# M9A_12_3190102060_A.net
KiCad netlist of a schematic drawn in Altium Designer
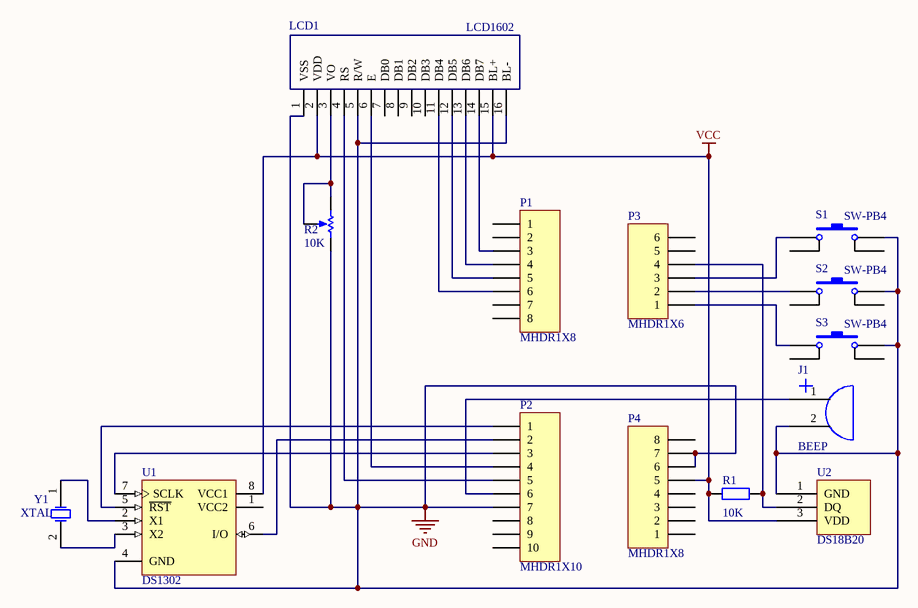
[diagram p0: M9A_12_3190102060_A.SchDoc]

(export (version "E")
  (design (tool "Eeschema 10.0.6"))
  (components
    (comp (ref "J1")
      (value "BEEP")
      (footprint "Beep")
      (description "蜂鸣器")
      (libsource (lib "Fszhang") (part "BEEP"))
    )
    (comp (ref "LCD1") (value "LCD1602") (footprint "1602") (libsource (lib "LCD") (part "LCD1602")))
    (comp (ref "P1")
      (value "MHDR1X8")
      (footprint "HDR1X8")
      (description "Header, 8-Pin")
      (fields (field (name "PUBLISHER") "Altium Limited"))
      (libsource (lib "Miscellaneous Connectors") (part "MHDR1X8"))
    )
    (comp (ref "P2")
      (value "MHDR1X10")
      (footprint "HDR1X10")
      (description "Header, 10-Pin")
      (fields (field (name "PUBLISHER") "Altium Limited"))
      (libsource (lib "Miscellaneous Connectors") (part "MHDR1X10"))
    )
    (comp (ref "P3")
      (value "MHDR1X6")
      (footprint "HDR1X6")
      (description "Header, 6-Pin")
      (fields (field (name "PUBLISHER") "Altium Limited"))
      (libsource (lib "Miscellaneous Connectors") (part "MHDR1X6"))
    )
    (comp (ref "P4")
      (value "MHDR1X8")
      (footprint "HDR1X8")
      (description "Header, 8-Pin")
      (fields (field (name "PUBLISHER") "Altium Limited"))
      (libsource (lib "") (part "MHDR1X8_1"))
    )
    (comp (ref "R1")
      (value "10K")
      (footprint "AXIAL-0.4")
      (description "Resistor")
      (fields (field (name "Comment") "Res2") (field (name "PUBLISHER") "Altium Limited"))
      (libsource (lib "Miscellaneous Devices") (part "Res2"))
    )
    (comp (ref "R2")
      (value "10K")
      (footprint "VR_A1")
      (description "精密可调电阻")
      (fields (field (name "Comment") "RPot") (field (name "PUBLISHER") "Altium Limited"))
      (libsource (lib "Fszhang") (part "RPot"))
    )
    (comp (ref "S1")
      (value "SW-PB4")
      (footprint "AN-S")
      (description "微动开关")
      (fields (field (name "PUBLISHER") "Altium Limited"))
      (libsource (lib "Fszhang") (part "SW-PB4"))
    )
    (comp (ref "S2")
      (value "SW-PB4")
      (footprint "AN-S")
      (description "微动开关")
      (fields (field (name "PUBLISHER") "Altium Limited"))
      (libsource (lib "Fszhang") (part "SW-PB4"))
    )
    (comp (ref "S3")
      (value "SW-PB4")
      (footprint "AN-S")
      (description "微动开关")
      (fields (field (name "PUBLISHER") "Altium Limited"))
      (libsource (lib "Fszhang") (part "SW-PB4"))
    )
    (comp (ref "U1")
      (value "DS1302")
      (footprint "DIP8")
      (description "Trickle Charge Timekeeping Chip")
      (fields (field (name "PUBLISHER") "Altium Limited"))
      (libsource (lib "Dallas Peripheral Real Time Clock") (part "DS1302"))
    )
    (comp (ref "U2")
      (value "DS18B20")
      (footprint "TO-92A")
      (description "温度传感器")
      (libsource (lib "Fszhang") (part "DS18B20"))
    )
    (comp (ref "Y1")
      (value "XTAL")
      (footprint "R38")
      (description "Crystal Oscillator")
      (fields (field (name "PUBLISHER") "Altium Limited"))
      (libsource (lib "Miscellaneous Devices") (part "XTAL"))
    )
  )
  (nets
    (net (code "1") (name "GND") (class "Default")
      (node (ref "J1") (pin "2") (pinfunction "1_2") (pintype "passive"))
      (node (ref "LCD1") (pin "1") (pinfunction "VSS_1") (pintype "passive"))
      (node (ref "LCD1") (pin "16") (pinfunction "BL-_16") (pintype "passive"))
      (node (ref "LCD1") (pin "5") (pinfunction "R/W_5") (pintype "passive"))
      (node (ref "P2") (pin "7") (pinfunction "7_7") (pintype "passive"))
      (node (ref "P4") (pin "6") (pinfunction "6_6") (pintype "passive"))
      (node (ref "P4") (pin "7") (pinfunction "7_7") (pintype "passive"))
      (node (ref "R2") (pin "3") (pinfunction "BOT_3") (pintype "passive"))
      (node (ref "S1") (pin "2") (pinfunction "2_2") (pintype "passive"))
      (node (ref "S2") (pin "2") (pinfunction "2_2") (pintype "passive"))
      (node (ref "S3") (pin "2") (pinfunction "2_2") (pintype "passive"))
      (node (ref "U1") (pin "4") (pinfunction "GND_4") (pintype "power_in"))
      (node (ref "U2") (pin "1") (pinfunction "GND_1") (pintype "passive"))
    )
    (net (code "2") (name "Net-(J1-0)") (class "Default")
      (node (ref "J1") (pin "1") (pinfunction "0_1") (pintype "passive"))
      (node (ref "P2") (pin "6") (pinfunction "6_6") (pintype "passive"))
    )
    (net (code "3") (name "Net-(LCD1-DB4)") (class "Default")
      (node (ref "LCD1") (pin "11") (pinfunction "DB4_11") (pintype "passive"))
      (node (ref "P1") (pin "6") (pinfunction "6_6") (pintype "passive"))
    )
    (net (code "4") (name "Net-(LCD1-DB5)") (class "Default")
      (node (ref "LCD1") (pin "12") (pinfunction "DB5_12") (pintype "passive"))
      (node (ref "P1") (pin "5") (pinfunction "5_5") (pintype "passive"))
    )
    (net (code "5") (name "Net-(LCD1-DB6)") (class "Default")
      (node (ref "LCD1") (pin "13") (pinfunction "DB6_13") (pintype "passive"))
      (node (ref "P1") (pin "4") (pinfunction "4_4") (pintype "passive"))
    )
    (net (code "6") (name "Net-(LCD1-DB7)") (class "Default")
      (node (ref "LCD1") (pin "14") (pinfunction "DB7_14") (pintype "passive"))
      (node (ref "P1") (pin "3") (pinfunction "3_3") (pintype "passive"))
    )
    (net (code "7") (name "Net-(LCD1-E)") (class "Default")
      (node (ref "LCD1") (pin "6") (pinfunction "E_6") (pintype "passive"))
      (node (ref "P2") (pin "4") (pinfunction "4_4") (pintype "passive"))
    )
    (net (code "8") (name "Net-(LCD1-RS)") (class "Default")
      (node (ref "LCD1") (pin "4") (pinfunction "RS_4") (pintype "passive"))
      (node (ref "P2") (pin "5") (pinfunction "5_5") (pintype "passive"))
    )
    (net (code "9") (name "Net-(LCD1-VO)") (class "Default")
      (node (ref "LCD1") (pin "3") (pinfunction "VO_3") (pintype "passive"))
      (node (ref "R2") (pin "1") (pinfunction "TOP_1") (pintype "passive"))
      (node (ref "R2") (pin "2") (pinfunction "TAP_2") (pintype "passive"))
    )
    (net (code "10") (name "Net-(P3-Pad1)") (class "Default")
      (node (ref "P3") (pin "1") (pinfunction "1_1") (pintype "passive"))
      (node (ref "S3") (pin "1") (pinfunction "1_1") (pintype "passive"))
    )
    (net (code "11") (name "Net-(P3-Pad2)") (class "Default")
      (node (ref "P3") (pin "2") (pinfunction "2_2") (pintype "passive"))
      (node (ref "S2") (pin "1") (pinfunction "1_1") (pintype "passive"))
    )
    (net (code "12") (name "Net-(P3-Pad3)") (class "Default")
      (node (ref "P3") (pin "3") (pinfunction "3_3") (pintype "passive"))
      (node (ref "S1") (pin "1") (pinfunction "1_1") (pintype "passive"))
    )
    (net (code "13") (name "Net-(U1-I{slash}O)") (class "Default")
      (node (ref "P2") (pin "2") (pinfunction "2_2") (pintype "passive"))
      (node (ref "U1") (pin "6") (pinfunction "I/O_6") (pintype "bidirectional"))
    )
    (net (code "14") (name "Net-(U1-SCLK)") (class "Default")
      (node (ref "P2") (pin "3") (pinfunction "3_3") (pintype "passive"))
      (node (ref "U1") (pin "7") (pinfunction "SCLK_7") (pintype "input"))
    )
    (net (code "15") (name "Net-(U1-X1)") (class "Default")
      (node (ref "U1") (pin "2") (pinfunction "X1_2") (pintype "input"))
      (node (ref "Y1") (pin "1") (pinfunction "OSC1_1") (pintype "passive"))
    )
    (net (code "16") (name "Net-(U1-X2)") (class "Default")
      (node (ref "U1") (pin "3") (pinfunction "X2_3") (pintype "input"))
      (node (ref "Y1") (pin "2") (pinfunction "OSC2_2") (pintype "passive"))
    )
    (net (code "17") (name "Net-(U1-~{RST})") (class "Default")
      (node (ref "P2") (pin "1") (pinfunction "1_1") (pintype "passive"))
      (node (ref "U1") (pin "5") (pinfunction "~{RST}_5") (pintype "input"))
    )
    (net (code "18") (name "Net-(U2-DQ)") (class "Default")
      (node (ref "P3") (pin "4") (pinfunction "4_4") (pintype "passive"))
      (node (ref "R1") (pin "2") (pinfunction "2_2") (pintype "passive"))
      (node (ref "U2") (pin "2") (pinfunction "DQ_2") (pintype "passive"))
    )
    (net (code "19") (name "VCC") (class "Default")
      (node (ref "LCD1") (pin "15") (pinfunction "BL+_15") (pintype "passive"))
      (node (ref "LCD1") (pin "2") (pinfunction "VDD_2") (pintype "passive"))
      (node (ref "P4") (pin "5") (pinfunction "5_5") (pintype "passive"))
      (node (ref "R1") (pin "1") (pinfunction "1_1") (pintype "passive"))
      (node (ref "U1") (pin "8") (pinfunction "VCC1_8") (pintype "power_in"))
      (node (ref "U2") (pin "3") (pinfunction "VDD_3") (pintype "passive"))
    )
    (net (code "20") (name "unconnected-(LCD1-DB0-Pad7)") (class "Default")
      (node (ref "LCD1") (pin "7") (pinfunction "DB0_7") (pintype "passive"))
    )
    (net (code "21") (name "unconnected-(LCD1-DB1-Pad8)") (class "Default")
      (node (ref "LCD1") (pin "8") (pinfunction "DB1_8") (pintype "passive"))
    )
    (net (code "22") (name "unconnected-(LCD1-DB2-Pad9)") (class "Default")
      (node (ref "LCD1") (pin "9") (pinfunction "DB2_9") (pintype "passive"))
    )
    (net (code "23") (name "unconnected-(LCD1-DB3-Pad10)") (class "Default")
      (node (ref "LCD1") (pin "10") (pinfunction "DB3_10") (pintype "passive"))
    )
    (net (code "24") (name "unconnected-(P1-Pad1)") (class "Default")
      (node (ref "P1") (pin "1") (pinfunction "1_1") (pintype "passive"))
    )
    (net (code "25") (name "unconnected-(P1-Pad2)") (class "Default")
      (node (ref "P1") (pin "2") (pinfunction "2_2") (pintype "passive"))
    )
    (net (code "26") (name "unconnected-(P1-Pad7)") (class "Default")
      (node (ref "P1") (pin "7") (pinfunction "7_7") (pintype "passive"))
    )
    (net (code "27") (name "unconnected-(P1-Pad8)") (class "Default")
      (node (ref "P1") (pin "8") (pinfunction "8_8") (pintype "passive"))
    )
    (net (code "28") (name "unconnected-(P2-Pad8)") (class "Default")
      (node (ref "P2") (pin "8") (pinfunction "8_8") (pintype "passive"))
    )
    (net (code "29") (name "unconnected-(P2-Pad9)") (class "Default")
      (node (ref "P2") (pin "9") (pinfunction "9_9") (pintype "passive"))
    )
    (net (code "30") (name "unconnected-(P2-Pad10)") (class "Default")
      (node (ref "P2") (pin "10") (pinfunction "10_10") (pintype "passive"))
    )
    (net (code "31") (name "unconnected-(P3-Pad5)") (class "Default")
      (node (ref "P3") (pin "5") (pinfunction "5_5") (pintype "passive"))
    )
    (net (code "32") (name "unconnected-(P3-Pad6)") (class "Default")
      (node (ref "P3") (pin "6") (pinfunction "6_6") (pintype "passive"))
    )
    (net (code "33") (name "unconnected-(P4-Pad1)") (class "Default")
      (node (ref "P4") (pin "1") (pinfunction "1_1") (pintype "passive"))
    )
    (net (code "34") (name "unconnected-(P4-Pad2)") (class "Default")
      (node (ref "P4") (pin "2") (pinfunction "2_2") (pintype "passive"))
    )
    (net (code "35") (name "unconnected-(P4-Pad3)") (class "Default")
      (node (ref "P4") (pin "3") (pinfunction "3_3") (pintype "passive"))
    )
    (net (code "36") (name "unconnected-(P4-Pad4)") (class "Default")
      (node (ref "P4") (pin "4") (pinfunction "4_4") (pintype "passive"))
    )
    (net (code "37") (name "unconnected-(P4-Pad8)") (class "Default")
      (node (ref "P4") (pin "8") (pinfunction "8_8") (pintype "passive"))
    )
    (net (code "38") (name "unconnected-(S1-Pad3)") (class "Default")
      (node (ref "S1") (pin "3") (pinfunction "3_3") (pintype "passive"))
    )
    (net (code "39") (name "unconnected-(S1-Pad4)") (class "Default")
      (node (ref "S1") (pin "4") (pinfunction "4_4") (pintype "passive"))
    )
    (net (code "40") (name "unconnected-(S2-Pad3)") (class "Default")
      (node (ref "S2") (pin "3") (pinfunction "3_3") (pintype "passive"))
    )
    (net (code "41") (name "unconnected-(S2-Pad4)") (class "Default")
      (node (ref "S2") (pin "4") (pinfunction "4_4") (pintype "passive"))
    )
    (net (code "42") (name "unconnected-(S3-Pad3)") (class "Default")
      (node (ref "S3") (pin "3") (pinfunction "3_3") (pintype "passive"))
    )
    (net (code "43") (name "unconnected-(S3-Pad4)") (class "Default")
      (node (ref "S3") (pin "4") (pinfunction "4_4") (pintype "passive"))
    )
    (net (code "44") (name "unconnected-(U1-VCC2-Pad1)") (class "Default")
      (node (ref "U1") (pin "1") (pinfunction "VCC2_1") (pintype "power_in"))
    )
  )
)
